# Buck_60W20V_Control_Section.net
KiCad netlist of a schematic drawn in Altium Designer
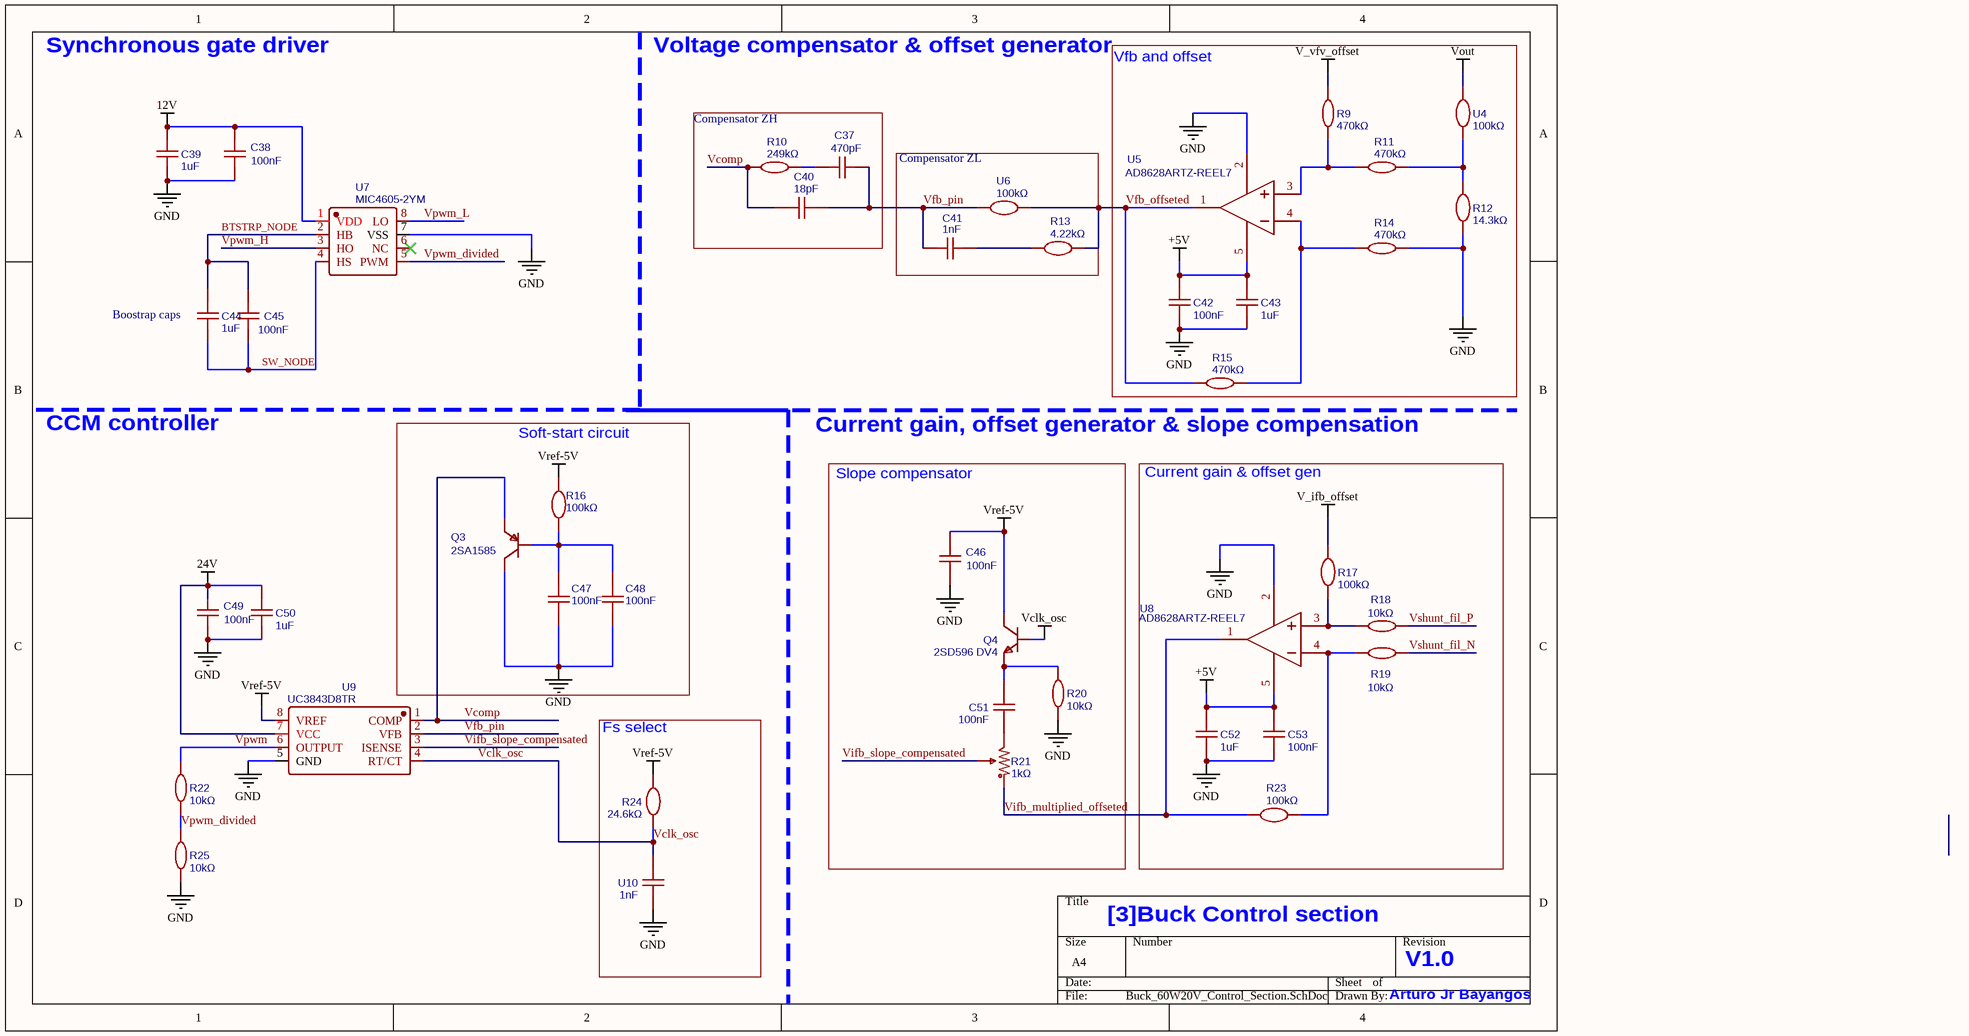
[diagram p0: Buck_60W20V_Control_Section.SchDoc]

(export (version "E")
  (design (tool "Eeschema 10.0.6"))
  (components
    (comp (ref "C37")
      (value "470pF")
      (footprint "C0603")
      (fields
        (field (name "MANUFACTURER") "YAGEO(国巨)")
        (field (name "MANUFACTURER PART") "CC0603GRNPO9BN471")
        (field (name "CONTRIBUTOR") "LCSC")
      )
      (libsource (lib "altium-import") (part "root_0_470pF_"))
    )
    (comp (ref "C38")
      (value "100nF")
      (footprint "C0402")
      (fields
        (field (name "MANUFACTURER") "TAIYO YUDEN(太诱)")
        (field (name "MANUFACTURER PART") "UMK105B7104KV-FR")
        (field (name "CONTRIBUTOR") "lcsc")
      )
      (libsource (lib "altium-import") (part "root_1_100nF_"))
    )
    (comp (ref "C39")
      (value "1uF")
      (footprint "C0603")
      (fields
        (field (name "MANUFACTURER") "TAIYO YUDEN(太诱)")
        (field (name "MANUFACTURER PART") "TMK107AB7105KAHT")
        (field (name "CONTRIBUTOR") "LCSC")
      )
      (libsource (lib "altium-import") (part "root_2_1uF_"))
    )
    (comp (ref "C40")
      (value "18pF")
      (footprint "C0603")
      (fields
        (field (name "MANUFACTURER") "Walsin(华新科)")
        (field (name "MANUFACTURER PART") "0603N180G500")
        (field (name "CONTRIBUTOR") "LCSC")
      )
      (libsource (lib "altium-import") (part "root_1_18pF_"))
    )
    (comp (ref "C41")
      (value "1nF")
      (footprint "C0603")
      (fields
        (field (name "MANUFACTURER") "YAGEO(国巨)")
        (field (name "MANUFACTURER PART") "CC0603GRNPO8BN102")
        (field (name "CONTRIBUTOR") "LCSC")
      )
      (libsource (lib "altium-import") (part "root_0_1nF_"))
    )
    (comp (ref "C42")
      (value "100nF")
      (footprint "C0402")
      (fields
        (field (name "MANUFACTURER") "TAIYO YUDEN(太诱)")
        (field (name "MANUFACTURER PART") "UMK105B7104KV-FR")
        (field (name "CONTRIBUTOR") "lcsc")
      )
      (libsource (lib "altium-import") (part "root_1_100nF_"))
    )
    (comp (ref "C43")
      (value "1uF")
      (footprint "C0603")
      (fields
        (field (name "MANUFACTURER") "TAIYO YUDEN(太诱)")
        (field (name "MANUFACTURER PART") "TMK107AB7105KAHT")
        (field (name "CONTRIBUTOR") "LCSC")
      )
      (libsource (lib "altium-import") (part "root_0_1uF_"))
    )
    (comp (ref "C44")
      (value "1uF")
      (footprint "C0603")
      (fields
        (field (name "MANUFACTURER") "TAIYO YUDEN(太诱)")
        (field (name "MANUFACTURER PART") "TMK107AB7105KAHT")
        (field (name "CONTRIBUTOR") "LCSC")
      )
      (libsource (lib "altium-import") (part "root_2_1uF_"))
    )
    (comp (ref "C45")
      (value "100nF")
      (footprint "C0402")
      (fields
        (field (name "MANUFACTURER") "TAIYO YUDEN(太诱)")
        (field (name "MANUFACTURER PART") "UMK105B7104KV-FR")
        (field (name "CONTRIBUTOR") "lcsc")
      )
      (libsource (lib "altium-import") (part "root_1_100nF_"))
    )
    (comp (ref "C46")
      (value "100nF")
      (footprint "C0402")
      (fields
        (field (name "MANUFACTURER") "TAIYO YUDEN(太诱)")
        (field (name "MANUFACTURER PART") "UMK105B7104KV-FR")
        (field (name "CONTRIBUTOR") "lcsc")
      )
      (libsource (lib "altium-import") (part "root_1_100nF_"))
    )
    (comp (ref "C47")
      (value "100nF")
      (footprint "C0402")
      (fields
        (field (name "MANUFACTURER") "TAIYO YUDEN(太诱)")
        (field (name "MANUFACTURER PART") "UMK105B7104KV-FR")
        (field (name "CONTRIBUTOR") "lcsc")
      )
      (libsource (lib "altium-import") (part "root_1_mirrored_100nF_"))
    )
    (comp (ref "C48")
      (value "100nF")
      (footprint "C0402")
      (fields
        (field (name "MANUFACTURER") "TAIYO YUDEN(太诱)")
        (field (name "MANUFACTURER PART") "UMK105B7104KV-FR")
        (field (name "CONTRIBUTOR") "lcsc")
      )
      (libsource (lib "altium-import") (part "root_1_mirrored_100nF_"))
    )
    (comp (ref "C49")
      (value "100nF")
      (footprint "C0402")
      (fields
        (field (name "MANUFACTURER") "TAIYO YUDEN(太诱)")
        (field (name "MANUFACTURER PART") "UMK105B7104KV-FR")
        (field (name "CONTRIBUTOR") "lcsc")
      )
      (libsource (lib "altium-import") (part "root_1_100nF_"))
    )
    (comp (ref "C50")
      (value "1uF")
      (footprint "C0603")
      (fields
        (field (name "MANUFACTURER") "TAIYO YUDEN(太诱)")
        (field (name "MANUFACTURER PART") "TMK107AB7105KAHT")
        (field (name "CONTRIBUTOR") "LCSC")
      )
      (libsource (lib "altium-import") (part "root_0_1uF_"))
    )
    (comp (ref "C51")
      (value "100nF")
      (footprint "C0402")
      (fields
        (field (name "MANUFACTURER") "TAIYO YUDEN(太诱)")
        (field (name "MANUFACTURER PART") "UMK105B7104KV-FR")
        (field (name "CONTRIBUTOR") "lcsc")
      )
      (libsource (lib "") (part "root_1_100nF__1"))
    )
    (comp (ref "C52")
      (value "1uF")
      (footprint "C0603")
      (fields
        (field (name "MANUFACTURER") "TAIYO YUDEN(太诱)")
        (field (name "MANUFACTURER PART") "TMK107AB7105KAHT")
        (field (name "CONTRIBUTOR") "LCSC")
      )
      (libsource (lib "altium-import") (part "root_0_1uF_"))
    )
    (comp (ref "C53")
      (value "100nF")
      (footprint "C0402")
      (fields
        (field (name "MANUFACTURER") "TAIYO YUDEN(太诱)")
        (field (name "MANUFACTURER PART") "UMK105B7104KV-FR")
        (field (name "CONTRIBUTOR") "lcsc")
      )
      (libsource (lib "altium-import") (part "root_1_100nF_"))
    )
    (comp (ref "Q3")
      (value "2SA1585")
      (footprint "SOT-23-3_L2.9-W1.6-P1.90-LS2.8-BR")
      (fields (field (name "MANUFACTURER") "CJ(江苏长电/长晶)"))
      (libsource (lib "altium-import") (part "root_0_mirrored_2SA1585_"))
    )
    (comp (ref "Q4")
      (value "2SD596 DV4")
      (footprint "SOT-23-3_L2.9-W1.6-P1.90-LS2.8-BR")
      (fields (field (name "MANUFACTURER") "CJ(江苏长电/长晶)") (field (name "MANUFACTURER PART") "2SD596"))
      (libsource (lib "altium-import") (part "root_0_2SD596 DV4_"))
    )
    (comp (ref "R9")
      (value "470kΩ")
      (footprint "R0603")
      (fields
        (field (name "MANUFACTURER") "Viking(光颉)")
        (field (name "MANUFACTURER PART") "AR03BTCX4703")
        (field (name "CONTRIBUTOR") "LCSC")
      )
      (libsource (lib "altium-import") (part "root_1_470kΩ_"))
    )
    (comp (ref "R10")
      (value "249kΩ")
      (footprint "R0603")
      (fields
        (field (name "MANUFACTURER") "Viking(光颉)")
        (field (name "MANUFACTURER PART") "ARG03FTC2493")
        (field (name "CONTRIBUTOR") "LCSC")
      )
      (libsource (lib "altium-import") (part "root_2_249kΩ_"))
    )
    (comp (ref "R11")
      (value "470kΩ")
      (footprint "R0603")
      (fields
        (field (name "MANUFACTURER") "Viking(光颉)")
        (field (name "MANUFACTURER PART") "AR03BTCX4703")
        (field (name "CONTRIBUTOR") "LCSC")
      )
      (libsource (lib "altium-import") (part "root_0_470kΩ_"))
    )
    (comp (ref "R12")
      (value "14.3kΩ")
      (footprint "R0603")
      (fields
        (field (name "MANUFACTURER") "YAGEO(国巨)")
        (field (name "MANUFACTURER PART") "RT0603BRE0714K3L")
        (field (name "CONTRIBUTOR") "LCSC")
      )
      (libsource (lib "altium-import") (part "root_1_14.3kΩ_"))
    )
    (comp (ref "R13")
      (value "4.22kΩ")
      (footprint "R0603")
      (fields
        (field (name "MANUFACTURER") "VISHAY(威世)")
        (field (name "MANUFACTURER PART") "CRCW06034K22FKEA")
        (field (name "CONTRIBUTOR") "LCSC")
      )
      (libsource (lib "altium-import") (part "root_0_4.22kΩ_"))
    )
    (comp (ref "R14")
      (value "470kΩ")
      (footprint "R0603")
      (fields
        (field (name "MANUFACTURER") "Viking(光颉)")
        (field (name "MANUFACTURER PART") "AR03BTCX4703")
        (field (name "CONTRIBUTOR") "LCSC")
      )
      (libsource (lib "altium-import") (part "root_0_470kΩ_"))
    )
    (comp (ref "R15")
      (value "470kΩ")
      (footprint "R0603")
      (fields
        (field (name "MANUFACTURER") "Viking(光颉)")
        (field (name "MANUFACTURER PART") "AR03BTCX4703")
        (field (name "CONTRIBUTOR") "LCSC")
      )
      (libsource (lib "altium-import") (part "root_0_470kΩ_"))
    )
    (comp (ref "R16")
      (value "100kΩ")
      (footprint "R0603")
      (fields
        (field (name "MANUFACTURER") "Viking(光颉)")
        (field (name "MANUFACTURER PART") "ARG03BTC1003")
        (field (name "CONTRIBUTOR") "LCSC")
      )
      (libsource (lib "altium-import") (part "root_1_mirrored_100kΩ_"))
    )
    (comp (ref "R17")
      (value "100kΩ")
      (footprint "R0603")
      (fields
        (field (name "MANUFACTURER") "Viking(光颉)")
        (field (name "MANUFACTURER PART") "ARG03BTC1003")
        (field (name "CONTRIBUTOR") "LCSC")
      )
      (libsource (lib "altium-import") (part "root_1_100kΩ_"))
    )
    (comp (ref "R18")
      (value "10kΩ")
      (footprint "R0603")
      (fields
        (field (name "MANUFACTURER") "Viking(光颉)")
        (field (name "MANUFACTURER PART") "ARG03BTC1002")
        (field (name "CONTRIBUTOR") "LCSC")
      )
      (libsource (lib "altium-import") (part "root_0_10kΩ_"))
    )
    (comp (ref "R19")
      (value "10kΩ")
      (footprint "R0603")
      (fields
        (field (name "MANUFACTURER") "Viking(光颉)")
        (field (name "MANUFACTURER PART") "ARG03BTC1002")
        (field (name "CONTRIBUTOR") "LCSC")
      )
      (libsource (lib "altium-import") (part "root_0_10kΩ_"))
    )
    (comp (ref "R20")
      (value "10kΩ")
      (footprint "R0603")
      (fields
        (field (name "MANUFACTURER") "Viking(光颉)")
        (field (name "MANUFACTURER PART") "ARG03BTC1002")
        (field (name "CONTRIBUTOR") "LCSC")
      )
      (libsource (lib "altium-import") (part "root_1_10kΩ_"))
    )
    (comp (ref "R21")
      (value "1kΩ")
      (footprint "RES-ADJ-TH_3296W")
      (fields
        (field (name "MANUFACTURER") "BOCHEN(博晨)")
        (field (name "MANUFACTURER PART") "3296W-1-102-8mm")
        (field (name "CONTRIBUTOR") "LCSC")
      )
      (libsource (lib "altium-import") (part "root_3_1kΩ_"))
    )
    (comp (ref "R22")
      (value "10kΩ")
      (footprint "R0603")
      (fields
        (field (name "MANUFACTURER") "Viking(光颉)")
        (field (name "MANUFACTURER PART") "ARG03BTC1002")
        (field (name "CONTRIBUTOR") "LCSC")
      )
      (libsource (lib "altium-import") (part "root_1_10kΩ_"))
    )
    (comp (ref "R23")
      (value "100kΩ")
      (footprint "R0603")
      (fields
        (field (name "MANUFACTURER") "Viking(光颉)")
        (field (name "MANUFACTURER PART") "ARG03BTC1003")
        (field (name "CONTRIBUTOR") "LCSC")
      )
      (libsource (lib "altium-import") (part "root_0_100kΩ_"))
    )
    (comp (ref "R24")
      (value "24.6kΩ")
      (footprint "R0603")
      (fields
        (field (name "MANUFACTURER") "YAGEO(国巨)")
        (field (name "MANUFACTURER PART") "RT0603BRD0724K6L")
        (field (name "CONTRIBUTOR") "lcsc")
      )
      (libsource (lib "altium-import") (part "root_1_24.6kΩ_"))
    )
    (comp (ref "R25")
      (value "10kΩ")
      (footprint "R0603")
      (fields
        (field (name "MANUFACTURER") "Viking(光颉)")
        (field (name "MANUFACTURER PART") "ARG03BTC1002")
        (field (name "CONTRIBUTOR") "LCSC")
      )
      (libsource (lib "altium-import") (part "root_1_10kΩ_"))
    )
    (comp (ref "U4")
      (value "100kΩ")
      (footprint "R0603")
      (fields
        (field (name "MANUFACTURER") "Milliohm(毫欧)")
        (field (name "MANUFACTURER PART") "HoAR0603-1/10W-100KR-0.1%-TCR25")
        (field (name "CONTRIBUTOR") "lcsc")
      )
      (libsource (lib "altium-import") (part "root_1_100kΩ_"))
    )
    (comp (ref "U5")
      (value "AD8628ARTZ-REEL7")
      (footprint "SOT-23-5_L3.0-W1.7-P0.95-LS2.8-BR")
      (fields (field (name "MANUFACTURER") "ADI(亚德诺)/LINEAR(凌特)"))
      (libsource (lib "altium-import") (part "root_0_AD8628ARTZ-REEL7_"))
    )
    (comp (ref "U6")
      (value "100kΩ")
      (footprint "R0603")
      (fields
        (field (name "MANUFACTURER") "Milliohm(毫欧)")
        (field (name "MANUFACTURER PART") "HoAR0603-1/10W-100KR-0.1%-TCR25")
        (field (name "CONTRIBUTOR") "lcsc")
      )
      (libsource (lib "altium-import") (part "root_2_100kΩ_"))
    )
    (comp (ref "U7")
      (value "MIC4605-2YM")
      (footprint "SOIC-8_L4.9-W3.9-P1.27-LS6.0-BL")
      (fields (field (name "MANUFACTURER") "MICROCHIP(美国微芯)") (field (name "CONTRIBUTOR") "lcsc"))
      (libsource (lib "altium-import") (part "root_0_MIC4605-2YM_"))
    )
    (comp (ref "U8")
      (value "AD8628ARTZ-REEL7")
      (footprint "SOT-23-5_L3.0-W1.7-P0.95-LS2.8-BR")
      (fields (field (name "MANUFACTURER") "ADI(亚德诺)/LINEAR(凌特)"))
      (libsource (lib "altium-import") (part "root_0_AD8628ARTZ-REEL7_"))
    )
    (comp (ref "U9")
      (value "UC3843D8TR")
      (footprint "SOIC-8_L4.9-W3.9-P1.27-LS6.0-TL")
      (fields (field (name "MANUFACTURER") "TI(德州仪器)") (field (name "CONTRIBUTOR") "LCSC"))
      (libsource (lib "altium-import") (part "root_0_UC3843D8TR_"))
    )
    (comp (ref "U10")
      (value "1nF")
      (footprint "C0201")
      (fields
        (field (name "MANUFACTURER") "muRata(村田)")
        (field (name "MANUFACTURER PART") "GRM0335C1E102GA01D")
        (field (name "CONTRIBUTOR") "lcsc")
      )
      (libsource (lib "altium-import") (part "root_1_1nF_"))
    )
  )
  (nets
    (net (code "1") (name "+5V") (class "Default")
      (node (ref "C42") (pin "2") (pinfunction "2_2") (pintype "passive"))
      (node (ref "C43") (pin "2") (pinfunction "2_2") (pintype "passive"))
      (node (ref "C52") (pin "2") (pinfunction "2_2") (pintype "passive"))
      (node (ref "C53") (pin "2") (pinfunction "2_2") (pintype "passive"))
      (node (ref "U5") (pin "5") (pinfunction "+V_5") (pintype "passive"))
      (node (ref "U8") (pin "5") (pinfunction "+V_5") (pintype "passive"))
    )
    (net (code "2") (name "/BTSTRP_NODE") (class "Default")
      (node (ref "C44") (pin "1") (pinfunction "1_1") (pintype "passive"))
      (node (ref "C45") (pin "2") (pinfunction "2_2") (pintype "passive"))
      (node (ref "U7") (pin "2") (pinfunction "HB_2") (pintype "passive"))
    )
    (net (code "3") (name "/SW_NODE") (class "Default")
      (node (ref "C44") (pin "2") (pinfunction "2_2") (pintype "passive"))
      (node (ref "C45") (pin "1") (pinfunction "1_1") (pintype "passive"))
      (node (ref "U7") (pin "4") (pinfunction "HS_4") (pintype "passive"))
    )
    (net (code "4") (name "/Vcomp") (class "Default")
      (node (ref "C40") (pin "2") (pinfunction "2_2") (pintype "passive"))
      (node (ref "Q3") (pin "2") (pinfunction "E_2") (pintype "passive"))
      (node (ref "R10") (pin "2") (pinfunction "2_2") (pintype "passive"))
      (node (ref "U9") (pin "1") (pinfunction "COMP_1") (pintype "passive"))
    )
    (net (code "5") (name "/Vfb_offseted") (class "Default")
      (node (ref "R13") (pin "2") (pinfunction "2_2") (pintype "passive"))
      (node (ref "R15") (pin "1") (pinfunction "1_1") (pintype "passive"))
      (node (ref "U5") (pin "1") (pinfunction "OUT_1") (pintype "passive"))
      (node (ref "U6") (pin "1") (pinfunction "1_1") (pintype "passive"))
    )
    (net (code "6") (name "/Vfb_pin") (class "Default")
      (node (ref "C37") (pin "2") (pinfunction "2_2") (pintype "passive"))
      (node (ref "C40") (pin "1") (pinfunction "1_1") (pintype "passive"))
      (node (ref "C41") (pin "1") (pinfunction "1_1") (pintype "passive"))
      (node (ref "U6") (pin "2") (pinfunction "2_2") (pintype "passive"))
      (node (ref "U9") (pin "2") (pinfunction "VFB_2") (pintype "passive"))
    )
    (net (code "7") (name "/Vifb_multiplied_offseted") (class "Default")
      (node (ref "R21") (pin "1") (pinfunction "1_1") (pintype "passive"))
      (node (ref "R23") (pin "1") (pinfunction "1_1") (pintype "passive"))
      (node (ref "U8") (pin "1") (pinfunction "OUT_1") (pintype "passive"))
    )
    (net (code "8") (name "/Vifb_slope_compensated") (class "Default")
      (node (ref "R21") (pin "2") (pinfunction "2_2") (pintype "passive"))
      (node (ref "U9") (pin "3") (pinfunction "ISENSE_3") (pintype "passive"))
    )
    (net (code "9") (name "/Vpwm") (class "Default")
      (node (ref "R22") (pin "2") (pinfunction "2_2") (pintype "passive"))
      (node (ref "U9") (pin "6") (pinfunction "OUTPUT_6") (pintype "passive"))
    )
    (net (code "10") (name "/Vpwm_H") (class "Default")
      (node (ref "U7") (pin "3") (pinfunction "HO_3") (pintype "passive"))
    )
    (net (code "11") (name "/Vpwm_L") (class "Default")
      (node (ref "U7") (pin "8") (pinfunction "LO_8") (pintype "passive"))
    )
    (net (code "12") (name "/Vpwm_divided") (class "Default")
      (node (ref "R22") (pin "1") (pinfunction "1_1") (pintype "passive"))
      (node (ref "R25") (pin "2") (pinfunction "2_2") (pintype "passive"))
      (node (ref "U7") (pin "5") (pinfunction "PWM_5") (pintype "passive"))
    )
    (net (code "13") (name "/Vshunt_fil_N") (class "Default")
      (node (ref "R19") (pin "2") (pinfunction "2_2") (pintype "passive"))
    )
    (net (code "14") (name "/Vshunt_fil_P") (class "Default")
      (node (ref "R18") (pin "2") (pinfunction "2_2") (pintype "passive"))
    )
    (net (code "15") (name "12V") (class "Default")
      (node (ref "C38") (pin "2") (pinfunction "2_2") (pintype "passive"))
      (node (ref "C39") (pin "1") (pinfunction "1_1") (pintype "passive"))
      (node (ref "U7") (pin "1") (pinfunction "VDD_1") (pintype "passive"))
    )
    (net (code "16") (name "24V") (class "Default")
      (node (ref "C49") (pin "2") (pinfunction "2_2") (pintype "passive"))
      (node (ref "C50") (pin "2") (pinfunction "2_2") (pintype "passive"))
      (node (ref "U9") (pin "7") (pinfunction "VCC_7") (pintype "passive"))
    )
    (net (code "17") (name "GND") (class "Default")
      (node (ref "C38") (pin "1") (pinfunction "1_1") (pintype "passive"))
      (node (ref "C39") (pin "2") (pinfunction "2_2") (pintype "passive"))
      (node (ref "C42") (pin "1") (pinfunction "1_1") (pintype "passive"))
      (node (ref "C43") (pin "1") (pinfunction "1_1") (pintype "passive"))
      (node (ref "C46") (pin "1") (pinfunction "1_1") (pintype "passive"))
      (node (ref "C47") (pin "1") (pinfunction "1_1") (pintype "passive"))
      (node (ref "C48") (pin "1") (pinfunction "1_1") (pintype "passive"))
      (node (ref "C49") (pin "1") (pinfunction "1_1") (pintype "passive"))
      (node (ref "C50") (pin "1") (pinfunction "1_1") (pintype "passive"))
      (node (ref "C52") (pin "1") (pinfunction "1_1") (pintype "passive"))
      (node (ref "C53") (pin "1") (pinfunction "1_1") (pintype "passive"))
      (node (ref "Q3") (pin "3") (pinfunction "C_3") (pintype "passive"))
      (node (ref "R12") (pin "1") (pinfunction "1_1") (pintype "passive"))
      (node (ref "R14") (pin "2") (pinfunction "2_2") (pintype "passive"))
      (node (ref "R20") (pin "1") (pinfunction "1_1") (pintype "passive"))
      (node (ref "R25") (pin "1") (pinfunction "1_1") (pintype "passive"))
      (node (ref "U10") (pin "1") (pinfunction "1_1") (pintype "passive"))
      (node (ref "U5") (pin "2") (pinfunction "-V_2") (pintype "passive"))
      (node (ref "U7") (pin "7") (pinfunction "VSS_7") (pintype "passive"))
      (node (ref "U8") (pin "2") (pinfunction "-V_2") (pintype "passive"))
      (node (ref "U9") (pin "5") (pinfunction "GND_5") (pintype "passive"))
    )
    (net (code "18") (name "Net-(C37-Pad1)") (class "Default")
      (node (ref "C37") (pin "1") (pinfunction "1_1") (pintype "passive"))
      (node (ref "R10") (pin "1") (pinfunction "1_1") (pintype "passive"))
    )
    (net (code "19") (name "Net-(C41-Pad2)") (class "Default")
      (node (ref "C41") (pin "2") (pinfunction "2_2") (pintype "passive"))
      (node (ref "R13") (pin "1") (pinfunction "1_1") (pintype "passive"))
    )
    (net (code "20") (name "Net-(C51-Pad1)") (class "Default")
      (node (ref "C51") (pin "1") (pinfunction "1_1") (pintype "passive"))
      (node (ref "R21") (pin "3") (pinfunction "3_3") (pintype "passive"))
    )
    (net (code "21") (name "Net-(Q3-B)") (class "Default")
      (node (ref "C47") (pin "2") (pinfunction "2_2") (pintype "passive"))
      (node (ref "C48") (pin "2") (pinfunction "2_2") (pintype "passive"))
      (node (ref "Q3") (pin "1") (pinfunction "B_1") (pintype "passive"))
      (node (ref "R16") (pin "1") (pinfunction "1_1") (pintype "passive"))
    )
    (net (code "22") (name "Net-(Q4-E)") (class "Default")
      (node (ref "C51") (pin "2") (pinfunction "2_2") (pintype "passive"))
      (node (ref "Q4") (pin "2") (pinfunction "E_2") (pintype "passive"))
      (node (ref "R20") (pin "2") (pinfunction "2_2") (pintype "passive"))
    )
    (net (code "23") (name "Net-(R11-Pad2)") (class "Default")
      (node (ref "R11") (pin "2") (pinfunction "2_2") (pintype "passive"))
      (node (ref "R12") (pin "2") (pinfunction "2_2") (pintype "passive"))
      (node (ref "U4") (pin "1") (pinfunction "1_1") (pintype "passive"))
    )
    (net (code "24") (name "Net-(U5-+IN)") (class "Default")
      (node (ref "R11") (pin "1") (pinfunction "1_1") (pintype "passive"))
      (node (ref "R9") (pin "1") (pinfunction "1_1") (pintype "passive"))
      (node (ref "U5") (pin "3") (pinfunction "+IN_3") (pintype "passive"))
    )
    (net (code "25") (name "Net-(U5--IN)") (class "Default")
      (node (ref "R14") (pin "1") (pinfunction "1_1") (pintype "passive"))
      (node (ref "R15") (pin "2") (pinfunction "2_2") (pintype "passive"))
      (node (ref "U5") (pin "4") (pinfunction "-IN_4") (pintype "passive"))
    )
    (net (code "26") (name "Net-(U8-+IN)") (class "Default")
      (node (ref "R17") (pin "1") (pinfunction "1_1") (pintype "passive"))
      (node (ref "R18") (pin "1") (pinfunction "1_1") (pintype "passive"))
      (node (ref "U8") (pin "3") (pinfunction "+IN_3") (pintype "passive"))
    )
    (net (code "27") (name "Net-(U8--IN)") (class "Default")
      (node (ref "R19") (pin "1") (pinfunction "1_1") (pintype "passive"))
      (node (ref "R23") (pin "2") (pinfunction "2_2") (pintype "passive"))
      (node (ref "U8") (pin "4") (pinfunction "-IN_4") (pintype "passive"))
    )
    (net (code "28") (name "V_ifb_offset") (class "Default")
      (node (ref "R17") (pin "2") (pinfunction "2_2") (pintype "passive"))
    )
    (net (code "29") (name "V_vfv_offset") (class "Default")
      (node (ref "R9") (pin "2") (pinfunction "2_2") (pintype "passive"))
    )
    (net (code "30") (name "Vclk_osc") (class "Default")
      (node (ref "Q4") (pin "1") (pinfunction "B_1") (pintype "passive"))
      (node (ref "R24") (pin "1") (pinfunction "1_1") (pintype "passive"))
      (node (ref "U10") (pin "2") (pinfunction "2_2") (pintype "passive"))
      (node (ref "U9") (pin "4") (pinfunction "RT/CT_4") (pintype "passive"))
    )
    (net (code "31") (name "Vout") (class "Default")
      (node (ref "U4") (pin "2") (pinfunction "2_2") (pintype "passive"))
    )
    (net (code "32") (name "Vref-5V") (class "Default")
      (node (ref "C46") (pin "2") (pinfunction "2_2") (pintype "passive"))
      (node (ref "Q4") (pin "3") (pinfunction "C_3") (pintype "passive"))
      (node (ref "R16") (pin "2") (pinfunction "2_2") (pintype "passive"))
      (node (ref "R24") (pin "2") (pinfunction "2_2") (pintype "passive"))
      (node (ref "U9") (pin "8") (pinfunction "VREF_8") (pintype "passive"))
    )
    (net (code "33") (name "unconnected-(U7-NC-Pad6)") (class "Default")
      (node (ref "U7") (pin "6") (pinfunction "NC_6") (pintype "passive+no_connect"))
    )
  )
)
